# esp_neopixel.net
KiCad netlist of a schematic drawn in EAGLE
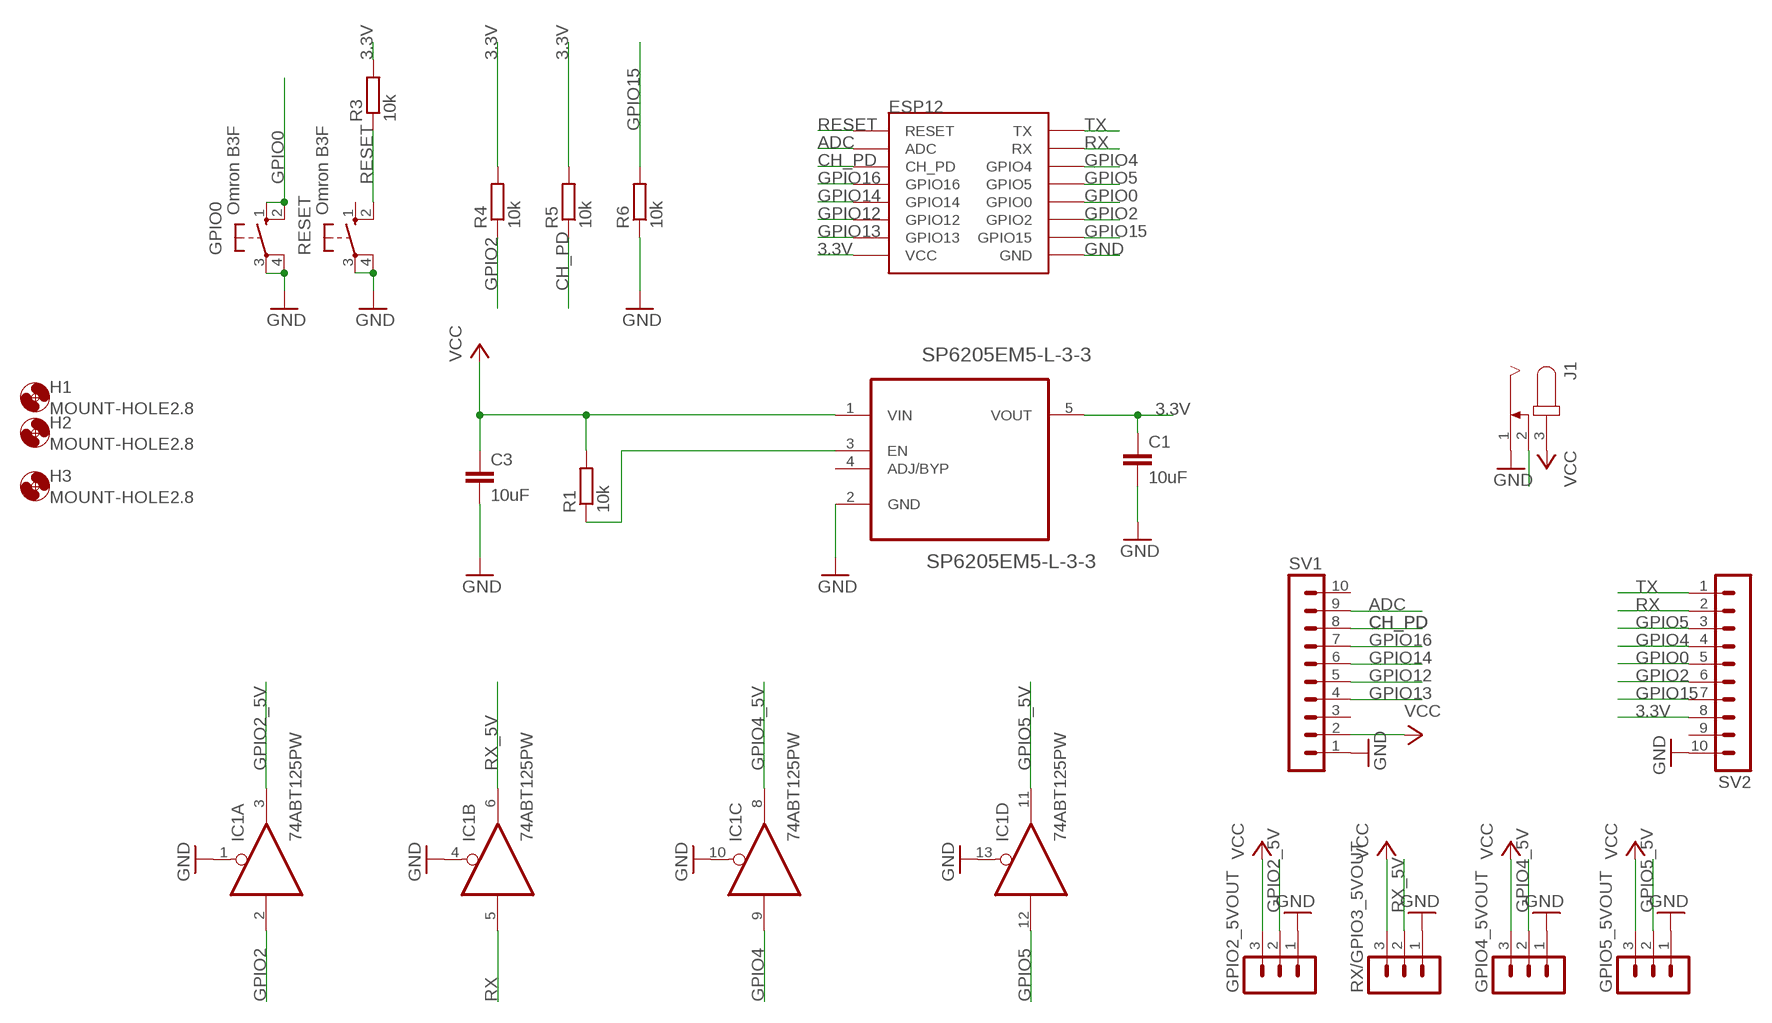
[diagram p0: schematic, sheet 1]

(export (version "E")
  (design (tool "Eeschema 10.0.6"))
  (components
    (comp (ref "C1")
      (value "10uF")
      (footprint "eagle-import:C0805K")
      (libsource (lib "eagle-import") (part "C-EUC0805K"))
    )
    (comp (ref "C3")
      (value "10uF")
      (footprint "eagle-import:C0805K")
      (libsource (lib "eagle-import") (part "C-EUC0805K"))
    )
    (comp (ref "ESP12")
      (value "ESP12")
      (footprint "eagle-import:ESP12")
      (libsource (lib "eagle-import") (part "ESP12"))
    )
    (comp (ref "GPIO0")
      (value "Omron B3F")
      (footprint "eagle-import:B3F-10XX")
      (fields (field (name "MPN") "B3F-1000"))
      (libsource (lib "eagle-import") (part "10-XX"))
    )
    (comp (ref "GPIO2_5VOUT")
      (value "MA03-1")
      (footprint "eagle-import:MA03-1")
      (libsource (lib "eagle-import") (part "MA03-1"))
    )
    (comp (ref "GPIO4_5VOUT")
      (value "MA03-1")
      (footprint "eagle-import:MA03-1")
      (libsource (lib "eagle-import") (part "MA03-1"))
    )
    (comp (ref "GPIO5_5VOUT")
      (value "MA03-1")
      (footprint "eagle-import:MA03-1")
      (libsource (lib "eagle-import") (part "MA03-1"))
    )
    (comp (ref "H1")
      (value "MOUNT-HOLE2.8")
      (footprint "eagle-import:2,8")
      (libsource (lib "eagle-import") (part "MOUNT-HOLE2.8"))
    )
    (comp (ref "H2")
      (value "MOUNT-HOLE2.8")
      (footprint "eagle-import:2,8")
      (libsource (lib "eagle-import") (part "MOUNT-HOLE2.8"))
    )
    (comp (ref "H3")
      (value "MOUNT-HOLE2.8")
      (footprint "eagle-import:2,8")
      (libsource (lib "eagle-import") (part "MOUNT-HOLE2.8"))
    )
    (comp (ref "IC1")
      (value "74ABT125PW")
      (footprint "eagle-import:TSSOP14")
      (libsource (lib "eagle-import") (part "74125PWABT"))
    )
    (comp (ref "J1")
      (value "JACK-PLUG1")
      (footprint "eagle-import:SPC4078")
      (libsource (lib "eagle-import") (part "JACK-PLUG1"))
    )
    (comp (ref "R1")
      (value "10k")
      (footprint "eagle-import:M0805")
      (libsource (lib "eagle-import") (part "R-EU_M0805"))
    )
    (comp (ref "R3")
      (value "10k")
      (footprint "eagle-import:M0805")
      (libsource (lib "eagle-import") (part "R-EU_M0805"))
    )
    (comp (ref "R4")
      (value "10k")
      (footprint "eagle-import:M0805")
      (libsource (lib "eagle-import") (part "R-EU_M0805"))
    )
    (comp (ref "R5")
      (value "10k")
      (footprint "eagle-import:M0805")
      (libsource (lib "eagle-import") (part "R-EU_M0805"))
    )
    (comp (ref "R6")
      (value "10k")
      (footprint "eagle-import:M0805")
      (libsource (lib "eagle-import") (part "R-EU_M0805"))
    )
    (comp (ref "RESET")
      (value "Omron B3F")
      (footprint "eagle-import:B3F-10XX")
      (fields (field (name "MPN") "B3F-1000"))
      (libsource (lib "eagle-import") (part "10-XX"))
    )
    (comp (ref "RX/GPIO3_5VOUT")
      (value "MA03-1")
      (footprint "eagle-import:MA03-1")
      (libsource (lib "eagle-import") (part "MA03-1"))
    )
    (comp (ref "SP6205EM5-L-3-3")
      (value "SP6205EM5-L-3-3")
      (footprint "eagle-import:SOT95P280X145-5N")
      (fields (field (name "MPN") "SPX3819M5-L"))
      (libsource (lib "eagle-import") (part "SPX3819M5-L"))
    )
    (comp (ref "SV1")
      (value "MA10-1W")
      (footprint "eagle-import:MA10-1W")
      (libsource (lib "eagle-import") (part "MA10-1W"))
    )
    (comp (ref "SV2")
      (value "MA10-1W")
      (footprint "eagle-import:MA10-1W")
      (libsource (lib "eagle-import") (part "MA10-1W"))
    )
  )
  (nets
    (net (code "1") (name "/3.3V") (class "Default")
      (node (ref "C1") (pin "1") (pinfunction "1_1") (pintype "passive"))
      (node (ref "ESP12") (pin "VCC") (pinfunction "VCC_VCC") (pintype "bidirectional"))
      (node (ref "R3") (pin "2") (pinfunction "2_2") (pintype "passive"))
      (node (ref "R4") (pin "2") (pinfunction "2_2") (pintype "passive"))
      (node (ref "R5") (pin "2") (pinfunction "2_2") (pintype "passive"))
      (node (ref "SP6205EM5-L-3-3") (pin "5") (pinfunction "VOUT_5") (pintype "output"))
      (node (ref "SV2") (pin "8") (pinfunction "8_8") (pintype "passive"))
    )
    (net (code "2") (name "/ADC") (class "Default")
      (node (ref "ESP12") (pin "ADC") (pinfunction "ADC_ADC") (pintype "bidirectional"))
      (node (ref "SV1") (pin "9") (pinfunction "9_9") (pintype "passive"))
    )
    (net (code "3") (name "/CH_PD") (class "Default")
      (node (ref "ESP12") (pin "CH_PD") (pinfunction "CH_PD_CH_PD") (pintype "bidirectional"))
      (node (ref "R5") (pin "1") (pinfunction "1_1") (pintype "passive"))
      (node (ref "SV1") (pin "8") (pinfunction "8_8") (pintype "passive"))
    )
    (net (code "4") (name "/GPIO0") (class "Default")
      (node (ref "ESP12") (pin "GPIO0") (pinfunction "GPIO0_GPIO0") (pintype "bidirectional"))
      (node (ref "GPIO0") (pin "1") (pinfunction "S_1") (pintype "passive"))
      (node (ref "GPIO0") (pin "2") (pinfunction "S1_2") (pintype "passive"))
      (node (ref "SV2") (pin "5") (pinfunction "5_5") (pintype "passive"))
    )
    (net (code "5") (name "/GPIO2") (class "Default")
      (node (ref "ESP12") (pin "GPIO2") (pinfunction "GPIO2_GPIO2") (pintype "bidirectional"))
      (node (ref "IC1") (pin "2") (pinfunction "I_2") (pintype "input"))
      (node (ref "R4") (pin "1") (pinfunction "1_1") (pintype "passive"))
      (node (ref "SV2") (pin "6") (pinfunction "6_6") (pintype "passive"))
    )
    (net (code "6") (name "/GPIO2_5V") (class "Default")
      (node (ref "GPIO2_5VOUT") (pin "2") (pinfunction "2_2") (pintype "passive"))
      (node (ref "IC1") (pin "3") (pinfunction "O_3") (pintype "tri_state"))
    )
    (net (code "7") (name "/GPIO4") (class "Default")
      (node (ref "ESP12") (pin "GPIO4") (pinfunction "GPIO4_GPIO4") (pintype "bidirectional"))
      (node (ref "IC1") (pin "9") (pinfunction "I_9") (pintype "input"))
      (node (ref "SV2") (pin "4") (pinfunction "4_4") (pintype "passive"))
    )
    (net (code "8") (name "/GPIO4_5V") (class "Default")
      (node (ref "GPIO4_5VOUT") (pin "2") (pinfunction "2_2") (pintype "passive"))
      (node (ref "IC1") (pin "8") (pinfunction "O_8") (pintype "tri_state"))
    )
    (net (code "9") (name "/GPIO5") (class "Default")
      (node (ref "ESP12") (pin "GPIO5") (pinfunction "GPIO5_GPIO5") (pintype "bidirectional"))
      (node (ref "IC1") (pin "12") (pinfunction "I_12") (pintype "input"))
      (node (ref "SV2") (pin "3") (pinfunction "3_3") (pintype "passive"))
    )
    (net (code "10") (name "/GPIO5_5V") (class "Default")
      (node (ref "GPIO5_5VOUT") (pin "2") (pinfunction "2_2") (pintype "passive"))
      (node (ref "IC1") (pin "11") (pinfunction "O_11") (pintype "tri_state"))
    )
    (net (code "11") (name "/GPIO12") (class "Default")
      (node (ref "ESP12") (pin "GPIO12") (pinfunction "GPIO12_GPIO12") (pintype "bidirectional"))
      (node (ref "SV1") (pin "5") (pinfunction "5_5") (pintype "passive"))
    )
    (net (code "12") (name "/GPIO13") (class "Default")
      (node (ref "ESP12") (pin "GPIO13") (pinfunction "GPIO13_GPIO13") (pintype "bidirectional"))
      (node (ref "SV1") (pin "4") (pinfunction "4_4") (pintype "passive"))
    )
    (net (code "13") (name "/GPIO14") (class "Default")
      (node (ref "ESP12") (pin "GPIO14") (pinfunction "GPIO14_GPIO14") (pintype "bidirectional"))
      (node (ref "SV1") (pin "6") (pinfunction "6_6") (pintype "passive"))
    )
    (net (code "14") (name "/GPIO15") (class "Default")
      (node (ref "ESP12") (pin "GPIO15") (pinfunction "GPIO15_GPIO15") (pintype "bidirectional"))
      (node (ref "R6") (pin "2") (pinfunction "2_2") (pintype "passive"))
      (node (ref "SV2") (pin "7") (pinfunction "7_7") (pintype "passive"))
    )
    (net (code "15") (name "/GPIO16") (class "Default")
      (node (ref "ESP12") (pin "GPIO16") (pinfunction "GPIO16_GPIO16") (pintype "bidirectional"))
      (node (ref "SV1") (pin "7") (pinfunction "7_7") (pintype "passive"))
    )
    (net (code "16") (name "/RESET") (class "Default")
      (node (ref "ESP12") (pin "RESET") (pinfunction "RESET_RESET") (pintype "bidirectional"))
      (node (ref "R3") (pin "1") (pinfunction "1_1") (pintype "passive"))
      (node (ref "RESET") (pin "2") (pinfunction "S1_2") (pintype "passive"))
    )
    (net (code "17") (name "/RX") (class "Default")
      (node (ref "ESP12") (pin "RX") (pinfunction "RX_RX") (pintype "bidirectional"))
      (node (ref "IC1") (pin "5") (pinfunction "I_5") (pintype "input"))
      (node (ref "SV2") (pin "2") (pinfunction "2_2") (pintype "passive"))
    )
    (net (code "18") (name "/RX_5V") (class "Default")
      (node (ref "IC1") (pin "6") (pinfunction "O_6") (pintype "tri_state"))
      (node (ref "RX/GPIO3_5VOUT") (pin "2") (pinfunction "2_2") (pintype "passive"))
    )
    (net (code "19") (name "/TX") (class "Default")
      (node (ref "ESP12") (pin "TX") (pinfunction "TX_TX") (pintype "bidirectional"))
      (node (ref "SV2") (pin "1") (pinfunction "1_1") (pintype "passive"))
    )
    (net (code "20") (name "GND") (class "Default")
      (node (ref "C1") (pin "2") (pinfunction "2_2") (pintype "passive"))
      (node (ref "C3") (pin "2") (pinfunction "2_2") (pintype "passive"))
      (node (ref "ESP12") (pin "GND") (pinfunction "GND_GND") (pintype "bidirectional"))
      (node (ref "GPIO0") (pin "3") (pinfunction "P_3") (pintype "passive"))
      (node (ref "GPIO0") (pin "4") (pinfunction "P1_4") (pintype "passive"))
      (node (ref "GPIO2_5VOUT") (pin "1") (pinfunction "1_1") (pintype "passive"))
      (node (ref "GPIO4_5VOUT") (pin "1") (pinfunction "1_1") (pintype "passive"))
      (node (ref "GPIO5_5VOUT") (pin "1") (pinfunction "1_1") (pintype "passive"))
      (node (ref "IC1") (pin "1") (pinfunction "OE_1") (pintype "input"))
      (node (ref "IC1") (pin "10") (pinfunction "OE_10") (pintype "input"))
      (node (ref "IC1") (pin "13") (pinfunction "OE_13") (pintype "input"))
      (node (ref "IC1") (pin "4") (pinfunction "OE_4") (pintype "input"))
      (node (ref "J1") (pin "1") (pinfunction "1_1") (pintype "passive"))
      (node (ref "R6") (pin "1") (pinfunction "1_1") (pintype "passive"))
      (node (ref "RESET") (pin "3") (pinfunction "P_3") (pintype "passive"))
      (node (ref "RESET") (pin "4") (pinfunction "P1_4") (pintype "passive"))
      (node (ref "RX/GPIO3_5VOUT") (pin "1") (pinfunction "1_1") (pintype "passive"))
      (node (ref "SP6205EM5-L-3-3") (pin "2") (pinfunction "GND_2") (pintype "passive"))
      (node (ref "SV1") (pin "1") (pinfunction "1_1") (pintype "passive"))
      (node (ref "SV2") (pin "10") (pinfunction "10_10") (pintype "passive"))
    )
    (net (code "21") (name "Net-(SP6205EM5-L-3-3-EN)") (class "Default")
      (node (ref "R1") (pin "1") (pinfunction "1_1") (pintype "passive"))
      (node (ref "SP6205EM5-L-3-3") (pin "3") (pinfunction "EN_3") (pintype "input"))
    )
    (net (code "22") (name "VCC") (class "Default")
      (node (ref "C3") (pin "1") (pinfunction "1_1") (pintype "passive"))
      (node (ref "GPIO2_5VOUT") (pin "3") (pinfunction "3_3") (pintype "passive"))
      (node (ref "GPIO4_5VOUT") (pin "3") (pinfunction "3_3") (pintype "passive"))
      (node (ref "GPIO5_5VOUT") (pin "3") (pinfunction "3_3") (pintype "passive"))
      (node (ref "J1") (pin "3") (pinfunction "3_3") (pintype "passive"))
      (node (ref "R1") (pin "2") (pinfunction "2_2") (pintype "passive"))
      (node (ref "RX/GPIO3_5VOUT") (pin "3") (pinfunction "3_3") (pintype "passive"))
      (node (ref "SP6205EM5-L-3-3") (pin "1") (pinfunction "VIN_1") (pintype "power_in"))
      (node (ref "SV1") (pin "2") (pinfunction "2_2") (pintype "passive"))
    )
    (net (code "23") (name "unconnected-(J1-Pad2)") (class "Default")
      (node (ref "J1") (pin "2") (pinfunction "2_2") (pintype "passive"))
    )
    (net (code "24") (name "unconnected-(RESET-S-Pad1)") (class "Default")
      (node (ref "RESET") (pin "1") (pinfunction "S_1") (pintype "passive"))
    )
    (net (code "25") (name "unconnected-(SP6205EM5-L-3-3-ADJ{slash}BYP-Pad4)") (class "Default")
      (node (ref "SP6205EM5-L-3-3") (pin "4") (pinfunction "ADJ/BYP_4") (pintype "passive"))
    )
    (net (code "26") (name "unconnected-(SV1-Pad3)") (class "Default")
      (node (ref "SV1") (pin "3") (pinfunction "3_3") (pintype "passive"))
    )
    (net (code "27") (name "unconnected-(SV1-Pad10)") (class "Default")
      (node (ref "SV1") (pin "10") (pinfunction "10_10") (pintype "passive"))
    )
    (net (code "28") (name "unconnected-(SV2-Pad9)") (class "Default")
      (node (ref "SV2") (pin "9") (pinfunction "9_9") (pintype "passive"))
    )
  )
)
